# ESP32_Schematic.net
KiCad netlist of a schematic drawn in Altium Designer
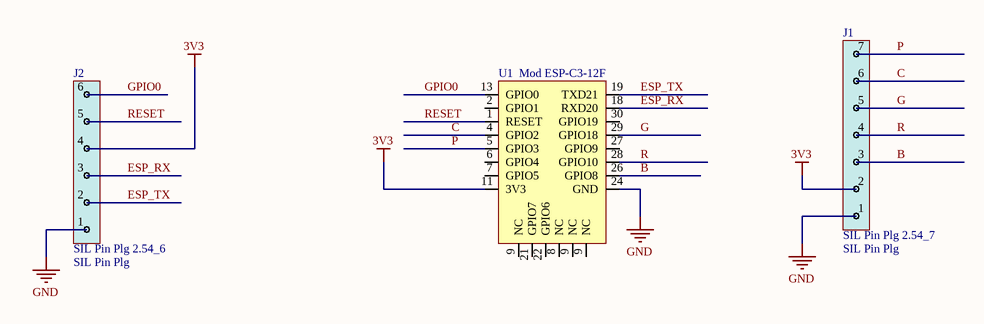
[diagram p0: ESP32 Schematic.SchDoc]

(export (version "E")
  (design (tool "Eeschema 10.0.6"))
  (components
    (comp (ref "J1")
      (value "SIL Pin Plg 2.54_7")
      (footprint "SIL PIN PLG 2.54_7")
      (description "7 Way SIL Pins")
      (fields (field (name "VOLTAGE") "250V") (field (name "TYPE") "SIL Pin Plg"))
      (libsource (lib "Connectors_SIL") (part "SIL Pin Plg 2.54_7"))
    )
    (comp (ref "J2")
      (value "SIL Pin Plg 2.54_6")
      (footprint "SIL PIN PLG 2.54_6")
      (description "6 Way SIL Pins")
      (fields (field (name "VOLTAGE") "250V") (field (name "TYPE") "SIL Pin Plg"))
      (libsource (lib "Connectors_SIL") (part "SIL Pin Plg 2.54_6"))
    )
    (comp (ref "U1")
      (value "Mod ESP-C3-12F")
      (footprint "ESP-C3-12F")
      (libsource (lib "Neds Altium Lib") (part "Mod ESP-C3-12F"))
    )
  )
  (nets
    (net (code "1") (name "/B") (class "Default")
      (node (ref "J1") (pin "3") (pinfunction "3_3") (pintype "passive"))
      (node (ref "U1") (pin "26") (pinfunction "GPIO8_26") (pintype "power_in"))
    )
    (net (code "2") (name "/C") (class "Default")
      (node (ref "J1") (pin "6") (pinfunction "6_6") (pintype "passive"))
      (node (ref "U1") (pin "4") (pinfunction "GPIO2_4") (pintype "power_in"))
    )
    (net (code "3") (name "/ESP_RX") (class "Default")
      (node (ref "J2") (pin "3") (pinfunction "3_3") (pintype "passive"))
      (node (ref "U1") (pin "18") (pinfunction "RXD20_18") (pintype "power_in"))
    )
    (net (code "4") (name "/ESP_TX") (class "Default")
      (node (ref "J2") (pin "2") (pinfunction "2_2") (pintype "passive"))
      (node (ref "U1") (pin "19") (pinfunction "TXD21_19") (pintype "power_in"))
    )
    (net (code "5") (name "/G") (class "Default")
      (node (ref "J1") (pin "5") (pinfunction "5_5") (pintype "passive"))
      (node (ref "U1") (pin "29") (pinfunction "GPIO18_29") (pintype "power_in"))
    )
    (net (code "6") (name "/GPIO0") (class "Default")
      (node (ref "J2") (pin "6") (pinfunction "6_6") (pintype "passive"))
      (node (ref "U1") (pin "13") (pinfunction "GPIO0_13") (pintype "power_in"))
    )
    (net (code "7") (name "/P") (class "Default")
      (node (ref "J1") (pin "7") (pinfunction "7_7") (pintype "passive"))
      (node (ref "U1") (pin "5") (pinfunction "GPIO3_5") (pintype "power_in"))
    )
    (net (code "8") (name "/R") (class "Default")
      (node (ref "J1") (pin "4") (pinfunction "4_4") (pintype "passive"))
      (node (ref "U1") (pin "28") (pinfunction "GPIO10_28") (pintype "power_in"))
    )
    (net (code "9") (name "/RESET") (class "Default")
      (node (ref "J2") (pin "5") (pinfunction "5_5") (pintype "passive"))
      (node (ref "U1") (pin "1") (pinfunction "RESET_1") (pintype "power_in"))
    )
    (net (code "10") (name "3V3") (class "Default")
      (node (ref "J1") (pin "2") (pinfunction "2_2") (pintype "passive"))
      (node (ref "J2") (pin "4") (pinfunction "4_4") (pintype "passive"))
      (node (ref "U1") (pin "11") (pinfunction "3V3_11") (pintype "power_in"))
    )
    (net (code "11") (name "GND") (class "Default")
      (node (ref "J1") (pin "1") (pinfunction "1_1") (pintype "passive"))
      (node (ref "J2") (pin "1") (pinfunction "1_1") (pintype "passive"))
      (node (ref "U1") (pin "24") (pinfunction "GND_24") (pintype "power_in"))
    )
    (net (code "12") (name "unconnected-(U1-GPIO1-Pad2)") (class "Default")
      (node (ref "U1") (pin "2") (pinfunction "GPIO1_2") (pintype "power_in"))
    )
    (net (code "13") (name "unconnected-(U1-GPIO4-Pad6)") (class "Default")
      (node (ref "U1") (pin "6") (pinfunction "GPIO4_6") (pintype "power_in"))
    )
    (net (code "14") (name "unconnected-(U1-GPIO5-Pad7)") (class "Default")
      (node (ref "U1") (pin "7") (pinfunction "GPIO5_7") (pintype "power_in"))
    )
    (net (code "15") (name "unconnected-(U1-GPIO6-Pad22)") (class "Default")
      (node (ref "U1") (pin "22") (pinfunction "GPIO6_22") (pintype "power_in"))
    )
    (net (code "16") (name "unconnected-(U1-GPIO7-Pad21)") (class "Default")
      (node (ref "U1") (pin "21") (pinfunction "GPIO7_21") (pintype "power_in"))
    )
    (net (code "17") (name "unconnected-(U1-GPIO9-Pad27)") (class "Default")
      (node (ref "U1") (pin "27") (pinfunction "GPIO9_27") (pintype "power_in"))
    )
    (net (code "18") (name "unconnected-(U1-GPIO19-Pad30)") (class "Default")
      (node (ref "U1") (pin "30") (pinfunction "GPIO19_30") (pintype "power_in"))
    )
    (net (code "19") (name "unconnected-(U1-NC-Pad8)") (class "Default")
      (node (ref "U1") (pin "8") (pinfunction "NC_8") (pintype "power_in"))
    )
    (net (code "20") (name "unconnected-(U1-NC-Pad9)") (class "Default")
      (node (ref "U1") (pin "9") (pinfunction "NC_9") (pintype "power_in"))
    )
    (net (code "21") (name "unconnected-(U1-NC-Pad9)_1") (class "Default")
      (node (ref "U1") (pin "9") (pinfunction "NC_9") (pintype "power_in"))
    )
    (net (code "22") (name "unconnected-(U1-NC-Pad9)_2") (class "Default")
      (node (ref "U1") (pin "9") (pinfunction "NC_9") (pintype "power_in"))
    )
  )
)
